# design.net
KiCad netlist of a schematic drawn in Altium Designer
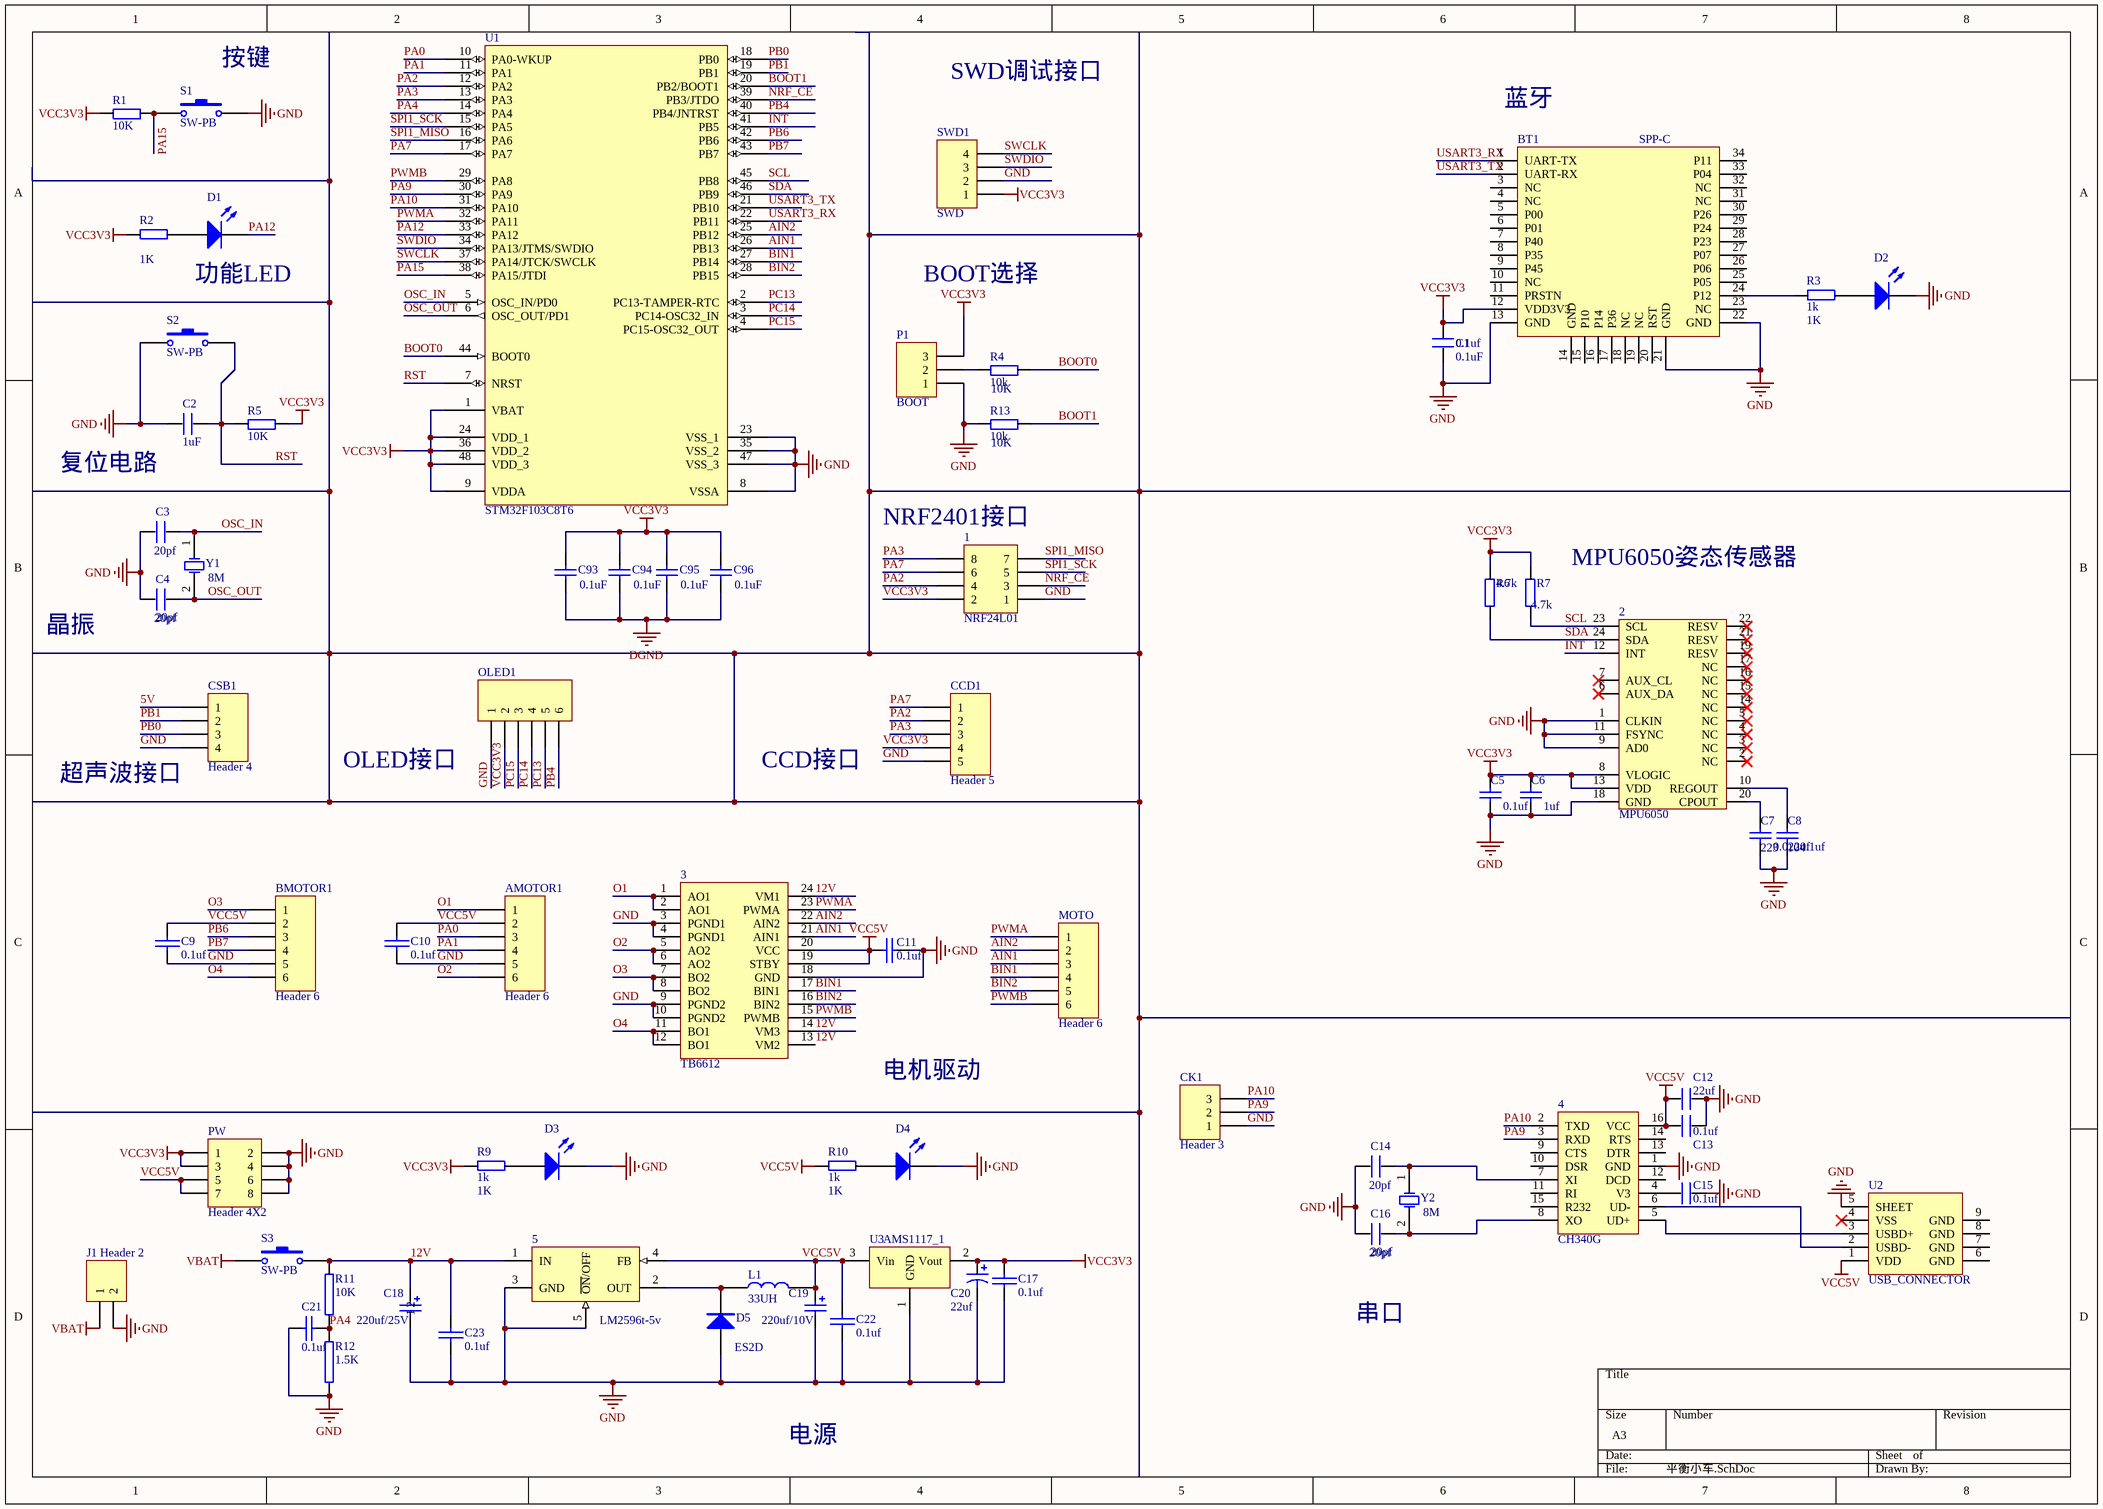
[diagram p0: 平衡小车.SchDoc]

(export (version "E")
  (design (tool "Eeschema 10.0.6"))
  (components
    (comp (ref "1")
      (value "NRF24L01")
      (footprint "LC-HDR2X4H")
      (description "Header, 4-Pin, Dual row, Right Angle")
      (fields (field (name "PUBLISHER") "Altium Limited"))
      (libsource (lib "Miscellaneous Connectors") (part "Header 4X2H"))
    )
    (comp (ref "2")
      (value "MPU6050")
      (footprint "LC-QFN-24_4x4x05P")
      (description "9轴运动处理传感器")
      (libsource (lib "Explorer STM32F407封装库") (part "MPU6050"))
    )
    (comp (ref "3") (value "TB6612") (footprint "TB6612") (libsource (lib "mzwlib") (part "TB6612")))
    (comp (ref "4") (value "CH340G") (footprint "SO-16") (libsource (lib "mzwlib") (part "CH340G")))
    (comp (ref "5")
      (value "LM2596t-5v")
      (footprint "LC-TO-263-5")
      (description "Simple Switcher 3A Step Down Voltage Regulator")
      (fields (field (name "PUBLISHER") "Altium Limited"))
      (libsource (lib "自创") (part "LM2576"))
    )
    (comp (ref "AMOTOR1")
      (value "Header 6")
      (footprint "HDR1X6")
      (description "Header, 6-Pin")
      (fields (field (name "PUBLISHER") "Altium Limited"))
      (libsource (lib "Miscellaneous Connectors") (part "Header 6"))
    )
    (comp (ref "BMOTOR1")
      (value "Header 6")
      (footprint "HDR1X6")
      (description "Header, 6-Pin")
      (fields (field (name "PUBLISHER") "Altium Limited"))
      (libsource (lib "Miscellaneous Connectors") (part "Header 6"))
    )
    (comp (ref "BT1")
      (value "SPP-C")
      (footprint "SPP-C")
      (description "sppc")
      (libsource (lib "mzwlib") (part "SPP-C"))
    )
    (comp (ref "C1")
      (value "0.1uf")
      (footprint "LC-0603_C")
      (fields (field (name "ALTIUM_VALUE") "0.1uF"))
      (libsource (lib "Explorer STM32F407封装库") (part "C"))
    )
    (comp (ref "C2")
      (value "1uF")
      (footprint "LC-0603_C")
      (libsource (lib "Explorer STM32F407封装库") (part "C_1"))
    )
    (comp (ref "C3")
      (value "20pf")
      (footprint "LC-0603_C")
      (libsource (lib "Explorer STM32F407封装库") (part "C"))
    )
    (comp (ref "C4")
      (value "20pf")
      (footprint "LC-0603_C")
      (fields (field (name "ALTIUM_VALUE") "20pf"))
      (libsource (lib "Explorer STM32F407封装库") (part "C"))
    )
    (comp (ref "C5")
      (value "0.1uf")
      (footprint "LC-0603_C")
      (description "Capacitor")
      (fields (field (name "PUBLISHER") "Altium Limited"))
      (libsource (lib "Miscellaneous Devices") (part "Cap"))
    )
    (comp (ref "C6")
      (value "1uf")
      (footprint "LC-0603_C")
      (description "Capacitor")
      (fields (field (name "PUBLISHER") "Altium Limited"))
      (libsource (lib "Miscellaneous Devices") (part "Cap"))
    )
    (comp (ref "C7")
      (value "0.022uf")
      (footprint "LC-0603_C")
      (description "Capacitor")
      (fields (field (name "ALTIUM_VALUE") "223") (field (name "PUBLISHER") "Altium Limited"))
      (libsource (lib "Miscellaneous Devices") (part "Cap"))
    )
    (comp (ref "C8")
      (value "0.1uf")
      (footprint "LC-0603_C")
      (description "Capacitor")
      (fields (field (name "ALTIUM_VALUE") "104") (field (name "PUBLISHER") "Altium Limited"))
      (libsource (lib "Miscellaneous Devices") (part "Cap"))
    )
    (comp (ref "C9") (value "0.1uf") (footprint "LC-0603_C") (libsource (lib "自创") (part "CAP")))
    (comp (ref "C10") (value "0.1uf") (footprint "LC-0603_C") (libsource (lib "自创") (part "CAP")))
    (comp (ref "C11") (value "0.1uf") (footprint "LC-0603_C") (libsource (lib "自创") (part "CAP")))
    (comp (ref "C12")
      (value "22uf")
      (footprint "LC-0805_C")
      (libsource (lib "Explorer STM32F407封装库") (part "C"))
    )
    (comp (ref "C13")
      (value "0.1uf")
      (footprint "LC-0603_C")
      (libsource (lib "Explorer STM32F407封装库") (part "C"))
    )
    (comp (ref "C14")
      (value "20pf")
      (footprint "LC-0603_C")
      (libsource (lib "Explorer STM32F407封装库") (part "C"))
    )
    (comp (ref "C15")
      (value "0.1uf")
      (footprint "LC-0603_C")
      (libsource (lib "Explorer STM32F407封装库") (part "C"))
    )
    (comp (ref "C16")
      (value "20pf")
      (footprint "LC-0603_C")
      (fields (field (name "ALTIUM_VALUE") "20pf"))
      (libsource (lib "Explorer STM32F407封装库") (part "C"))
    )
    (comp (ref "C17") (value "0.1uf") (footprint "LC-0603_C") (libsource (lib "自创") (part "CAP")))
    (comp (ref "C18")
      (value "220uf/25V")
      (footprint "100UF钽电容")
      (description "Polarized Capacitor (Radial)")
      (fields (field (name "Comment") "100Uf") (field (name "PUBLISHER") "Altium Limited"))
      (libsource (lib "") (part "Cap Pol1_1"))
    )
    (comp (ref "C19")
      (value "220uf/10V")
      (footprint "LC-1206_C")
      (description "Polarized Capacitor (Radial)")
      (fields (field (name "Comment") "100uf") (field (name "PUBLISHER") "Altium Limited"))
      (libsource (lib "自创") (part "Cap Pol1"))
    )
    (comp (ref "C20")
      (value "22uf")
      (footprint "LC-0805_R")
      (description "Polarized Capacitor (Axial)")
      (fields (field (name "PUBLISHER") "Altium Limited"))
      (libsource (lib "自创") (part "Cap Pol2"))
    )
    (comp (ref "C21") (value "0.1uf") (footprint "LC-0603_C") (libsource (lib "自创") (part "CAP")))
    (comp (ref "C22") (value "0.1uf") (footprint "LC-0603_C") (libsource (lib "自创") (part "CAP")))
    (comp (ref "C23") (value "0.1uf") (footprint "LC-0603_C") (libsource (lib "自创") (part "CAP")))
    (comp (ref "C93")
      (value "0.1uF")
      (footprint "LC-0603_C")
      (description "Capacitor")
      (fields (field (name "Comment") "0.1uf") (field (name "PUBLISHER") "Altium Limited"))
      (libsource (lib "Miscellaneous Devices") (part "Cap"))
    )
    (comp (ref "C94")
      (value "0.1uF")
      (footprint "LC-0603_C")
      (description "Capacitor")
      (fields (field (name "Comment") "0.1uf") (field (name "PUBLISHER") "Altium Limited"))
      (libsource (lib "Miscellaneous Devices") (part "Cap"))
    )
    (comp (ref "C95")
      (value "0.1uF")
      (footprint "LC-0603_C")
      (description "Capacitor")
      (fields (field (name "Comment") "0.1uf") (field (name "PUBLISHER") "Altium Limited"))
      (libsource (lib "Miscellaneous Devices") (part "Cap"))
    )
    (comp (ref "C96")
      (value "0.1uF")
      (footprint "LC-0603_C")
      (description "Capacitor")
      (fields (field (name "Comment") "0.1uf") (field (name "PUBLISHER") "Altium Limited"))
      (libsource (lib "Miscellaneous Devices") (part "Cap"))
    )
    (comp (ref "CCD1")
      (value "Header 5")
      (footprint "HDR1X5")
      (description "Header, 5-Pin")
      (fields (field (name "PUBLISHER") "Altium Limited"))
      (libsource (lib "Miscellaneous Connectors") (part "Header 5"))
    )
    (comp (ref "CK1")
      (value "Header 3")
      (footprint "HDR1X3")
      (description "Header, 3-Pin")
      (fields (field (name "PUBLISHER") "Altium Limited"))
      (libsource (lib "Miscellaneous Connectors") (part "Header 3"))
    )
    (comp (ref "CSB1")
      (value "Header 4")
      (footprint "HDR1X4")
      (description "Header, 4-Pin")
      (fields (field (name "PUBLISHER") "Altium Limited"))
      (libsource (lib "Miscellaneous Connectors") (part "Header 4"))
    )
    (comp (ref "D1")
      (value "LED0")
      (footprint "LC-0805_LED_S1")
      (description "Typical INFRARED GaAs LED")
      (fields (field (name "PUBLISHER") "Altium Limited"))
      (libsource (lib "Miscellaneous Devices") (part "LED0"))
    )
    (comp (ref "D2")
      (value "LED0")
      (footprint "LC-0805_LED_S1")
      (description "Typical INFRARED GaAs LED")
      (fields (field (name "PUBLISHER") "Altium Limited"))
      (libsource (lib "Miscellaneous Devices") (part "LED0"))
    )
    (comp (ref "D3")
      (value "LED0")
      (footprint "LC-0805_LED_S1")
      (description "Typical INFRARED GaAs LED")
      (fields (field (name "PUBLISHER") "Altium Limited"))
      (libsource (lib "Miscellaneous Devices") (part "LED0"))
    )
    (comp (ref "D4")
      (value "LED0")
      (footprint "LC-0805_LED_S1")
      (description "Typical INFRARED GaAs LED")
      (fields (field (name "PUBLISHER") "Altium Limited"))
      (libsource (lib "Miscellaneous Devices") (part "LED0"))
    )
    (comp (ref "D5") (value "ES2D") (footprint "LC-DO-213AB") (libsource (lib "自创") (part "DIODE")))
    (comp (ref "J1")
      (value "Header 2")
      (footprint "VBAT")
      (description "Header, 2-Pin")
      (fields (field (name "PUBLISHER") "Altium Limited"))
      (libsource (lib "Miscellaneous Connectors") (part "Header 2"))
    )
    (comp (ref "L1") (value "33UH") (footprint "330电感") (libsource (lib "自创") (part "Inductor")))
    (comp (ref "MOTO")
      (value "Header 6")
      (footprint "HDR1X6")
      (description "Header, 6-Pin")
      (fields (field (name "PUBLISHER") "Altium Limited"))
      (libsource (lib "Miscellaneous Connectors") (part "Header 6"))
    )
    (comp (ref "OLED1")
      (value "Header 6")
      (footprint "HDR1X6")
      (description "Header, 6-Pin")
      (fields (field (name "PUBLISHER") "Altium Limited"))
      (libsource (lib "") (part "Header 6_1"))
    )
    (comp (ref "P1")
      (value "BOOT")
      (footprint "HDR1X3")
      (description "Header, 3-Pin")
      (fields (field (name "PUBLISHER") "Altium Limited"))
      (libsource (lib "Miscellaneous Connectors") (part "Header 3"))
    )
    (comp (ref "PW")
      (value "Header 4X2")
      (footprint "HDR2X4")
      (description "Header, 4-Pin, Dual row")
      (fields (field (name "PUBLISHER") "Altium Limited"))
      (libsource (lib "Miscellaneous Connectors") (part "Header 4X2"))
    )
    (comp (ref "R1")
      (value "10K")
      (footprint "LC-0603_R")
      (libsource (lib "Explorer STM32F407封装库") (part "R_1"))
    )
    (comp (ref "R2")
      (value "1K")
      (footprint "LC-0603_R")
      (libsource (lib "Explorer STM32F407封装库") (part "R_1"))
    )
    (comp (ref "R3")
      (value "1k")
      (footprint "LC-0603_R")
      (fields (field (name "ALTIUM_VALUE") "1K"))
      (libsource (lib "Explorer STM32F407封装库") (part "R_1"))
    )
    (comp (ref "R4")
      (value "10k")
      (footprint "LC-0603_R")
      (fields (field (name "ALTIUM_VALUE") "10K"))
      (libsource (lib "Explorer STM32F407封装库") (part "R"))
    )
    (comp (ref "R5")
      (value "10K")
      (footprint "LC-0603_R")
      (libsource (lib "Explorer STM32F407封装库") (part "R_1"))
    )
    (comp (ref "R6")
      (value "4.7k")
      (footprint "LC-0603_R")
      (libsource (lib "Explorer STM32F407封装库") (part "R_1"))
    )
    (comp (ref "R7")
      (value "4.7k")
      (footprint "LC-0603_R")
      (libsource (lib "Explorer STM32F407封装库") (part "R_1"))
    )
    (comp (ref "R9")
      (value "1k")
      (footprint "LC-0603_R")
      (fields (field (name "ALTIUM_VALUE") "1K"))
      (libsource (lib "Explorer STM32F407封装库") (part "R_1"))
    )
    (comp (ref "R10")
      (value "1k")
      (footprint "LC-0603_R")
      (fields (field (name "ALTIUM_VALUE") "1K"))
      (libsource (lib "Explorer STM32F407封装库") (part "R_1"))
    )
    (comp (ref "R11") (value "10K") (footprint "LC-0603_R") (libsource (lib "自创") (part "RES")))
    (comp (ref "R12") (value "1.5K") (footprint "LC-0603_R") (libsource (lib "自创") (part "RES")))
    (comp (ref "R13")
      (value "10k")
      (footprint "LC-0603_R")
      (fields (field (name "ALTIUM_VALUE") "10K"))
      (libsource (lib "Explorer STM32F407封装库") (part "R"))
    )
    (comp (ref "S1")
      (value "SW-PB")
      (footprint "KEY")
      (description "Switch")
      (fields (field (name "PUBLISHER") "Altium Limited"))
      (libsource (lib "自创") (part "SW-PB"))
    )
    (comp (ref "S2")
      (value "SW-PB")
      (footprint "KEY")
      (description "Switch")
      (fields (field (name "PUBLISHER") "Altium Limited"))
      (libsource (lib "自创") (part "SW-PB"))
    )
    (comp (ref "S3")
      (value "SW-PB")
      (footprint "钮子开关")
      (description "Switch")
      (fields (field (name "PUBLISHER") "Altium Limited"))
      (libsource (lib "自创") (part "SW-PB"))
    )
    (comp (ref "SWD1")
      (value "SWD")
      (footprint "HDR1X4")
      (description "Header, 4-Pin")
      (fields (field (name "PUBLISHER") "Altium Limited"))
      (libsource (lib "") (part "Header 4_1"))
    )
    (comp (ref "U1")
      (value "STM32F103C8T6")
      (footprint "LC-LQFP-48_7x7x05P")
      (description "STM32 ARM-based 32-bit MCU with 64 Kbytes Flash, 48-pin LQFP, Industrial Temperature")
      (fields (field (name "PUBLISHER") "Altium Limited"))
      (libsource (lib "ST Microcontroller 32-Bit STM32") (part "STM32F103C8T6"))
    )
    (comp (ref "U2")
      (value "USB_CONNECTOR")
      (footprint "MINI_USB_FEMALE")
      (libsource (lib "mzwlib") (part "USB_CONNECTOR"))
    )
    (comp (ref "U3")
      (value "AMS1117_1")
      (footprint "LC-SOT-223")
      (description "3.3V电压转换器AMS1117")
      (libsource (lib "自创") (part "AMS1117_1"))
    )
    (comp (ref "Y1")
      (value "~")
      (footprint "LC-HC-49S")
      (description "Crystal Oscillator")
      (fields (field (name "ALTIUM_UNNAMED_1") "8M") (field (name "PUBLISHER") "Altium Limited"))
      (libsource (lib "Explorer STM32F407封装库") (part "XTAL"))
    )
    (comp (ref "Y2")
      (value "~")
      (footprint "LC-HC-49S")
      (description "Crystal Oscillator")
      (fields (field (name "ALTIUM_UNNAMED_1") "8M") (field (name "PUBLISHER") "Altium Limited"))
      (libsource (lib "Explorer STM32F407封装库") (part "XTAL"))
    )
  )
  (nets
    (net (code "1") (name "/5V") (class "Default")
      (node (ref "CSB1") (pin "1") (pinfunction "1_1") (pintype "passive"))
    )
    (net (code "2") (name "/12V") (class "Default")
      (node (ref "3") (pin "13") (pinfunction "VM2_13") (pintype "passive"))
      (node (ref "3") (pin "14") (pinfunction "VM3_14") (pintype "passive"))
      (node (ref "3") (pin "24") (pinfunction "VM1_24") (pintype "passive"))
      (node (ref "5") (pin "1") (pinfunction "IN_1") (pintype "power_in"))
      (node (ref "C18") (pin "1") (pinfunction "1_1") (pintype "passive"))
      (node (ref "C23") (pin "2") (pinfunction "2_2") (pintype "passive"))
      (node (ref "R11") (pin "2") (pinfunction "2_2") (pintype "passive"))
      (node (ref "S3") (pin "2") (pinfunction "2_2") (pintype "passive"))
    )
    (net (code "3") (name "/AIN1") (class "Default")
      (node (ref "3") (pin "21") (pinfunction "AIN1_21") (pintype "passive"))
      (node (ref "MOTO") (pin "3") (pinfunction "3_3") (pintype "passive"))
      (node (ref "U1") (pin "26") (pinfunction "PB13_26") (pintype "bidirectional"))
    )
    (net (code "4") (name "/AIN2") (class "Default")
      (node (ref "3") (pin "22") (pinfunction "AIN2_22") (pintype "passive"))
      (node (ref "MOTO") (pin "2") (pinfunction "2_2") (pintype "passive"))
      (node (ref "U1") (pin "25") (pinfunction "PB12_25") (pintype "bidirectional"))
    )
    (net (code "5") (name "/BIN1") (class "Default")
      (node (ref "3") (pin "17") (pinfunction "BIN1_17") (pintype "passive"))
      (node (ref "MOTO") (pin "4") (pinfunction "4_4") (pintype "passive"))
      (node (ref "U1") (pin "27") (pinfunction "PB14_27") (pintype "bidirectional"))
    )
    (net (code "6") (name "/BIN2") (class "Default")
      (node (ref "3") (pin "16") (pinfunction "BIN2_16") (pintype "passive"))
      (node (ref "MOTO") (pin "5") (pinfunction "5_5") (pintype "passive"))
      (node (ref "U1") (pin "28") (pinfunction "PB15_28") (pintype "bidirectional"))
    )
    (net (code "7") (name "/BOOT0") (class "Default")
      (node (ref "R4") (pin "2") (pintype "passive"))
      (node (ref "U1") (pin "44") (pinfunction "BOOT0_44") (pintype "input"))
    )
    (net (code "8") (name "/BOOT1") (class "Default")
      (node (ref "R13") (pin "2") (pintype "passive"))
      (node (ref "U1") (pin "20") (pinfunction "PB2/BOOT1_20") (pintype "bidirectional"))
    )
    (net (code "9") (name "/INT") (class "Default")
      (node (ref "2") (pin "12") (pinfunction "INT_12") (pintype "passive"))
      (node (ref "U1") (pin "41") (pinfunction "PB5_41") (pintype "bidirectional"))
    )
    (net (code "10") (name "/NRF_CE") (class "Default")
      (node (ref "1") (pin "3") (pinfunction "3_3") (pintype "passive"))
      (node (ref "U1") (pin "39") (pinfunction "PB3/JTDO_39") (pintype "bidirectional"))
    )
    (net (code "11") (name "/O1") (class "Default")
      (node (ref "3") (pin "1") (pinfunction "AO1_1") (pintype "passive"))
      (node (ref "3") (pin "2") (pinfunction "AO1_2") (pintype "passive"))
      (node (ref "AMOTOR1") (pin "1") (pinfunction "1_1") (pintype "passive"))
    )
    (net (code "12") (name "/O2") (class "Default")
      (node (ref "3") (pin "5") (pinfunction "AO2_5") (pintype "passive"))
      (node (ref "3") (pin "6") (pinfunction "AO2_6") (pintype "passive"))
      (node (ref "AMOTOR1") (pin "6") (pinfunction "6_6") (pintype "passive"))
    )
    (net (code "13") (name "/O3") (class "Default")
      (node (ref "3") (pin "7") (pinfunction "BO2_7") (pintype "passive"))
      (node (ref "3") (pin "8") (pinfunction "BO2_8") (pintype "passive"))
      (node (ref "BMOTOR1") (pin "1") (pinfunction "1_1") (pintype "passive"))
    )
    (net (code "14") (name "/O4") (class "Default")
      (node (ref "3") (pin "11") (pinfunction "BO1_11") (pintype "passive"))
      (node (ref "3") (pin "12") (pinfunction "BO1_12") (pintype "passive"))
      (node (ref "BMOTOR1") (pin "6") (pinfunction "6_6") (pintype "passive"))
    )
    (net (code "15") (name "/OSC_IN") (class "Default")
      (node (ref "C3") (pin "2") (pintype "passive"))
      (node (ref "U1") (pin "5") (pinfunction "OSC_IN/PD0_5") (pintype "input"))
      (node (ref "Y1") (pin "1") (pinfunction "OSC1_1") (pintype "passive"))
    )
    (net (code "16") (name "/OSC_OUT") (class "Default")
      (node (ref "C4") (pin "2") (pintype "passive"))
      (node (ref "U1") (pin "6") (pinfunction "OSC_OUT/PD1_6") (pintype "output"))
      (node (ref "Y1") (pin "2") (pinfunction "OSC2_2") (pintype "passive"))
    )
    (net (code "17") (name "/PA0") (class "Default")
      (node (ref "AMOTOR1") (pin "3") (pinfunction "3_3") (pintype "passive"))
      (node (ref "U1") (pin "10") (pinfunction "PA0-WKUP_10") (pintype "bidirectional"))
    )
    (net (code "18") (name "/PA1") (class "Default")
      (node (ref "AMOTOR1") (pin "4") (pinfunction "4_4") (pintype "passive"))
      (node (ref "U1") (pin "11") (pinfunction "PA1_11") (pintype "bidirectional"))
    )
    (net (code "19") (name "/PA2") (class "Default")
      (node (ref "1") (pin "4") (pinfunction "4_4") (pintype "passive"))
      (node (ref "CCD1") (pin "2") (pinfunction "2_2") (pintype "passive"))
      (node (ref "U1") (pin "12") (pinfunction "PA2_12") (pintype "bidirectional"))
    )
    (net (code "20") (name "/PA3") (class "Default")
      (node (ref "1") (pin "8") (pinfunction "8_8") (pintype "passive"))
      (node (ref "CCD1") (pin "3") (pinfunction "3_3") (pintype "passive"))
      (node (ref "U1") (pin "13") (pinfunction "PA3_13") (pintype "bidirectional"))
    )
    (net (code "21") (name "/PA4") (class "Default")
      (node (ref "C21") (pin "2") (pinfunction "2_2") (pintype "passive"))
      (node (ref "R11") (pin "1") (pinfunction "1_1") (pintype "passive"))
      (node (ref "R12") (pin "2") (pinfunction "2_2") (pintype "passive"))
      (node (ref "U1") (pin "14") (pinfunction "PA4_14") (pintype "bidirectional"))
    )
    (net (code "22") (name "/PA7") (class "Default")
      (node (ref "1") (pin "6") (pinfunction "6_6") (pintype "passive"))
      (node (ref "CCD1") (pin "1") (pinfunction "1_1") (pintype "passive"))
      (node (ref "U1") (pin "17") (pinfunction "PA7_17") (pintype "bidirectional"))
    )
    (net (code "23") (name "/PA9") (class "Default")
      (node (ref "4") (pin "3") (pinfunction "RXD_3") (pintype "passive"))
      (node (ref "CK1") (pin "2") (pinfunction "2_2") (pintype "passive"))
      (node (ref "U1") (pin "30") (pinfunction "PA9_30") (pintype "bidirectional"))
    )
    (net (code "24") (name "/PA10") (class "Default")
      (node (ref "4") (pin "2") (pinfunction "TXD_2") (pintype "passive"))
      (node (ref "CK1") (pin "3") (pinfunction "3_3") (pintype "passive"))
      (node (ref "U1") (pin "31") (pinfunction "PA10_31") (pintype "bidirectional"))
    )
    (net (code "25") (name "/PA12") (class "Default")
      (node (ref "D1") (pin "2") (pinfunction "K_2") (pintype "passive"))
      (node (ref "U1") (pin "33") (pinfunction "PA12_33") (pintype "bidirectional"))
    )
    (net (code "26") (name "/PA15") (class "Default")
      (node (ref "R1") (pin "2") (pintype "passive"))
      (node (ref "S1") (pin "1") (pinfunction "1_1") (pintype "passive"))
      (node (ref "U1") (pin "38") (pinfunction "PA15/JTDI_38") (pintype "bidirectional"))
    )
    (net (code "27") (name "/PB0") (class "Default")
      (node (ref "CSB1") (pin "3") (pinfunction "3_3") (pintype "passive"))
      (node (ref "U1") (pin "18") (pinfunction "PB0_18") (pintype "bidirectional"))
    )
    (net (code "28") (name "/PB1") (class "Default")
      (node (ref "CSB1") (pin "2") (pinfunction "2_2") (pintype "passive"))
      (node (ref "U1") (pin "19") (pinfunction "PB1_19") (pintype "bidirectional"))
    )
    (net (code "29") (name "/PB4") (class "Default")
      (node (ref "OLED1") (pin "6") (pinfunction "6_6") (pintype "passive"))
      (node (ref "U1") (pin "40") (pinfunction "PB4/JNTRST_40") (pintype "bidirectional"))
    )
    (net (code "30") (name "/PB6") (class "Default")
      (node (ref "BMOTOR1") (pin "3") (pinfunction "3_3") (pintype "passive"))
      (node (ref "U1") (pin "42") (pinfunction "PB6_42") (pintype "bidirectional"))
    )
    (net (code "31") (name "/PB7") (class "Default")
      (node (ref "BMOTOR1") (pin "4") (pinfunction "4_4") (pintype "passive"))
      (node (ref "U1") (pin "43") (pinfunction "PB7_43") (pintype "bidirectional"))
    )
    (net (code "32") (name "/PC13") (class "Default")
      (node (ref "OLED1") (pin "5") (pinfunction "5_5") (pintype "passive"))
      (node (ref "U1") (pin "2") (pinfunction "PC13-TAMPER-RTC_2") (pintype "bidirectional"))
    )
    (net (code "33") (name "/PC14") (class "Default")
      (node (ref "OLED1") (pin "4") (pinfunction "4_4") (pintype "passive"))
      (node (ref "U1") (pin "3") (pinfunction "PC14-OSC32_IN_3") (pintype "bidirectional"))
    )
    (net (code "34") (name "/PC15") (class "Default")
      (node (ref "OLED1") (pin "3") (pinfunction "3_3") (pintype "passive"))
      (node (ref "U1") (pin "4") (pinfunction "PC15-OSC32_OUT_4") (pintype "bidirectional"))
    )
    (net (code "35") (name "/PWMA") (class "Default")
      (node (ref "3") (pin "23") (pinfunction "PWMA_23") (pintype "passive"))
      (node (ref "MOTO") (pin "1") (pinfunction "1_1") (pintype "passive"))
      (node (ref "U1") (pin "32") (pinfunction "PA11_32") (pintype "bidirectional"))
    )
    (net (code "36") (name "/PWMB") (class "Default")
      (node (ref "3") (pin "15") (pinfunction "PWMB_15") (pintype "passive"))
      (node (ref "MOTO") (pin "6") (pinfunction "6_6") (pintype "passive"))
      (node (ref "U1") (pin "29") (pinfunction "PA8_29") (pintype "bidirectional"))
    )
    (net (code "37") (name "/RST") (class "Default")
      (node (ref "C2") (pin "2") (pintype "passive"))
      (node (ref "R5") (pin "1") (pintype "passive"))
      (node (ref "S2") (pin "2") (pinfunction "2_2") (pintype "passive"))
      (node (ref "U1") (pin "7") (pinfunction "NRST_7") (pintype "bidirectional"))
    )
    (net (code "38") (name "/SCL") (class "Default")
      (node (ref "2") (pin "23") (pinfunction "SCL_23") (pintype "passive"))
      (node (ref "R7") (pin "2") (pintype "passive"))
      (node (ref "U1") (pin "45") (pinfunction "PB8_45") (pintype "bidirectional"))
    )
    (net (code "39") (name "/SDA") (class "Default")
      (node (ref "2") (pin "24") (pinfunction "SDA_24") (pintype "passive"))
      (node (ref "R6") (pin "2") (pintype "passive"))
      (node (ref "U1") (pin "46") (pinfunction "PB9_46") (pintype "bidirectional"))
    )
    (net (code "40") (name "/SPI1_MISO") (class "Default")
      (node (ref "1") (pin "7") (pinfunction "7_7") (pintype "passive"))
      (node (ref "U1") (pin "16") (pinfunction "PA6_16") (pintype "bidirectional"))
    )
    (net (code "41") (name "/SPI1_SCK") (class "Default")
      (node (ref "1") (pin "5") (pinfunction "5_5") (pintype "passive"))
      (node (ref "U1") (pin "15") (pinfunction "PA5_15") (pintype "bidirectional"))
    )
    (net (code "42") (name "/SWCLK") (class "Default")
      (node (ref "SWD1") (pin "4") (pinfunction "4_4") (pintype "passive"))
      (node (ref "U1") (pin "37") (pinfunction "PA14/JTCK/SWCLK_37") (pintype "bidirectional"))
    )
    (net (code "43") (name "/SWDIO") (class "Default")
      (node (ref "SWD1") (pin "3") (pinfunction "3_3") (pintype "passive"))
      (node (ref "U1") (pin "34") (pinfunction "PA13/JTMS/SWDIO_34") (pintype "bidirectional"))
    )
    (net (code "44") (name "/USART3_RX") (class "Default")
      (node (ref "BT1") (pin "1") (pinfunction "UART-TX_1") (pintype "passive"))
      (node (ref "U1") (pin "22") (pinfunction "PB11_22") (pintype "bidirectional"))
    )
    (net (code "45") (name "/USART3_TX") (class "Default")
      (node (ref "BT1") (pin "2") (pinfunction "UART-RX_2") (pintype "passive"))
      (node (ref "U1") (pin "21") (pinfunction "PB10_21") (pintype "bidirectional"))
    )
    (net (code "46") (name "DGND") (class "Default")
      (node (ref "C93") (pin "1") (pinfunction "1_1") (pintype "passive"))
      (node (ref "C94") (pin "1") (pinfunction "1_1") (pintype "passive"))
      (node (ref "C95") (pin "1") (pinfunction "1_1") (pintype "passive"))
      (node (ref "C96") (pin "1") (pinfunction "1_1") (pintype "passive"))
    )
    (net (code "47") (name "GND") (class "Default")
      (node (ref "1") (pin "1") (pinfunction "1_1") (pintype "passive"))
      (node (ref "2") (pin "1") (pinfunction "CLKIN_1") (pintype "passive"))
      (node (ref "2") (pin "11") (pinfunction "FSYNC_11") (pintype "passive"))
      (node (ref "2") (pin "18") (pinfunction "GND_18") (pintype "passive"))
      (node (ref "2") (pin "9") (pinfunction "AD0_9") (pintype "passive"))
      (node (ref "3") (pin "10") (pinfunction "PGND2_10") (pintype "passive"))
      (node (ref "3") (pin "18") (pinfunction "GND_18") (pintype "passive"))
      (node (ref "3") (pin "3") (pinfunction "PGND1_3") (pintype "passive"))
      (node (ref "3") (pin "4") (pinfunction "PGND1_4") (pintype "passive"))
      (node (ref "3") (pin "9") (pinfunction "PGND2_9") (pintype "passive"))
      (node (ref "4") (pin "1") (pinfunction "GND_1") (pintype "passive"))
      (node (ref "5") (pin "3") (pinfunction "GND_3") (pintype "power_in"))
      (node (ref "5") (pin "5") (pinfunction "~{ON}/OFF_5") (pintype "input"))
      (node (ref "AMOTOR1") (pin "5") (pinfunction "5_5") (pintype "passive"))
      (node (ref "BMOTOR1") (pin "5") (pinfunction "5_5") (pintype "passive"))
      (node (ref "BT1") (pin "13") (pinfunction "GND_13") (pintype "passive"))
      (node (ref "BT1") (pin "21") (pinfunction "GND_21") (pintype "passive"))
      (node (ref "BT1") (pin "22") (pinfunction "GND_22") (pintype "passive"))
      (node (ref "C1") (pin "1") (pintype "passive"))
      (node (ref "C10") (pin "2") (pinfunction "2_2") (pintype "passive"))
      (node (ref "C11") (pin "1") (pinfunction "1_1") (pintype "passive"))
      (node (ref "C12") (pin "1") (pintype "passive"))
      (node (ref "C13") (pin "2") (pintype "passive"))
      (node (ref "C14") (pin "1") (pintype "passive"))
      (node (ref "C15") (pin "2") (pintype "passive"))
      (node (ref "C16") (pin "1") (pintype "passive"))
      (node (ref "C17") (pin "1") (pinfunction "1_1") (pintype "passive"))
      (node (ref "C18") (pin "2") (pinfunction "2_2") (pintype "passive"))
      (node (ref "C19") (pin "2") (pinfunction "2_2") (pintype "passive"))
      (node (ref "C2") (pin "1") (pintype "passive"))
      (node (ref "C20") (pin "2") (pinfunction "2_2") (pintype "passive"))
      (node (ref "C21") (pin "1") (pinfunction "1_1") (pintype "passive"))
      (node (ref "C22") (pin "1") (pinfunction "1_1") (pintype "passive"))
      (node (ref "C23") (pin "1") (pinfunction "1_1") (pintype "passive"))
      (node (ref "C3") (pin "1") (pintype "passive"))
      (node (ref "C4") (pin "1") (pintype "passive"))
      (node (ref "C5") (pin "1") (pinfunction "1_1") (pintype "passive"))
      (node (ref "C6") (pin "1") (pinfunction "1_1") (pintype "passive"))
      (node (ref "C7") (pin "1") (pinfunction "1_1") (pintype "passive"))
      (node (ref "C8") (pin "1") (pinfunction "1_1") (pintype "passive"))
      (node (ref "C9") (pin "2") (pinfunction "2_2") (pintype "passive"))
      (node (ref "CCD1") (pin "5") (pinfunction "5_5") (pintype "passive"))
      (node (ref "CK1") (pin "1") (pinfunction "1_1") (pintype "passive"))
      (node (ref "CSB1") (pin "4") (pinfunction "4_4") (pintype "passive"))
      (node (ref "D2") (pin "2") (pinfunction "K_2") (pintype "passive"))
      (node (ref "D3") (pin "2") (pinfunction "K_2") (pintype "passive"))
      (node (ref "D4") (pin "2") (pinfunction "K_2") (pintype "passive"))
      (node (ref "D5") (pin "1") (pinfunction "1_1") (pintype "passive"))
      (node (ref "J1") (pin "2") (pinfunction "2_2") (pintype "passive"))
      (node (ref "OLED1") (pin "1") (pinfunction "1_1") (pintype "passive"))
      (node (ref "P1") (pin "1") (pinfunction "1_1") (pintype "passive"))
      (node (ref "PW") (pin "2") (pinfunction "2_2") (pintype "passive"))
      (node (ref "PW") (pin "4") (pinfunction "4_4") (pintype "passive"))
      (node (ref "PW") (pin "6") (pinfunction "6_6") (pintype "passive"))
      (node (ref "PW") (pin "8") (pinfunction "8_8") (pintype "passive"))
      (node (ref "R12") (pin "1") (pinfunction "1_1") (pintype "passive"))
      (node (ref "R13") (pin "1") (pintype "passive"))
      (node (ref "S1") (pin "2") (pinfunction "2_2") (pintype "passive"))
      (node (ref "S2") (pin "1") (pinfunction "1_1") (pintype "passive"))
      (node (ref "SWD1") (pin "2") (pinfunction "2_2") (pintype "passive"))
      (node (ref "U1") (pin "23") (pinfunction "VSS_1_23") (pintype "power_in"))
      (node (ref "U1") (pin "35") (pinfunction "VSS_2_35") (pintype "power_in"))
      (node (ref "U1") (pin "47") (pinfunction "VSS_3_47") (pintype "power_in"))
      (node (ref "U1") (pin "8") (pinfunction "VSSA_8") (pintype "power_in"))
      (node (ref "U2") (pin "5") (pinfunction "SHEET_5") (pintype "passive"))
      (node (ref "U3") (pin "1") (pinfunction "GND_1") (pintype "passive"))
    )
    (net (code "48") (name "Net-(2-CPOUT)") (class "Default")
      (node (ref "2") (pin "20") (pinfunction "CPOUT_20") (pintype "passive"))
      (node (ref "C7") (pin "2") (pinfunction "2_2") (pintype "passive"))
    )
    (net (code "49") (name "Net-(2-REGOUT)") (class "Default")
      (node (ref "2") (pin "10") (pinfunction "REGOUT_10") (pintype "passive"))
      (node (ref "C8") (pin "2") (pinfunction "2_2") (pintype "passive"))
    )
    (net (code "50") (name "Net-(4-UD+)") (class "Default")
      (node (ref "4") (pin "5") (pinfunction "UD+_5") (pintype "passive"))
      (node (ref "U2") (pin "3") (pinfunction "USBD+_3") (pintype "passive"))
    )
    (net (code "51") (name "Net-(4-UD-)") (class "Default")
      (node (ref "4") (pin "6") (pinfunction "UD-_6") (pintype "passive"))
      (node (ref "U2") (pin "2") (pinfunction "USBD-_2") (pintype "passive"))
    )
    (net (code "52") (name "Net-(4-V3)") (class "Default")
      (node (ref "4") (pin "4") (pinfunction "V3_4") (pintype "passive"))
      (node (ref "C15") (pin "1") (pintype "passive"))
    )
    (net (code "53") (name "Net-(4-XI)") (class "Default")
      (node (ref "4") (pin "7") (pinfunction "XI_7") (pintype "passive"))
      (node (ref "C14") (pin "2") (pintype "passive"))
      (node (ref "Y2") (pin "1") (pinfunction "OSC1_1") (pintype "passive"))
    )
    (net (code "54") (name "Net-(4-XO)") (class "Default")
      (node (ref "4") (pin "8") (pinfunction "XO_8") (pintype "passive"))
      (node (ref "C16") (pin "2") (pintype "passive"))
      (node (ref "Y2") (pin "2") (pinfunction "OSC2_2") (pintype "passive"))
    )
    (net (code "55") (name "Net-(5-OUT)") (class "Default")
      (node (ref "5") (pin "2") (pinfunction "OUT_2") (pintype "power_in"))
      (node (ref "D5") (pin "2") (pinfunction "2_2") (pintype "passive"))
      (node (ref "L1") (pin "1") (pinfunction "1_1") (pintype "passive"))
    )
    (net (code "56") (name "Net-(BT1-P12)") (class "Default")
      (node (ref "BT1") (pin "24") (pinfunction "P12_24") (pintype "passive"))
      (node (ref "R3") (pin "2") (pintype "passive"))
    )
    (net (code "57") (name "Net-(D1-A)") (class "Default")
      (node (ref "D1") (pin "1") (pinfunction "A_1") (pintype "passive"))
      (node (ref "R2") (pin "1") (pintype "passive"))
    )
    (net (code "58") (name "Net-(D2-A)") (class "Default")
      (node (ref "D2") (pin "1") (pinfunction "A_1") (pintype "passive"))
      (node (ref "R3") (pin "1") (pintype "passive"))
    )
    (net (code "59") (name "Net-(D3-A)") (class "Default")
      (node (ref "D3") (pin "1") (pinfunction "A_1") (pintype "passive"))
      (node (ref "R9") (pin "1") (pintype "passive"))
    )
    (net (code "60") (name "Net-(D4-A)") (class "Default")
      (node (ref "D4") (pin "1") (pinfunction "A_1") (pintype "passive"))
      (node (ref "R10") (pin "1") (pintype "passive"))
    )
    (net (code "61") (name "Net-(P1-Pad2)") (class "Default")
      (node (ref "P1") (pin "2") (pinfunction "2_2") (pintype "passive"))
      (node (ref "R4") (pin "1") (pintype "passive"))
    )
    (net (code "62") (name "VBAT") (class "Default")
      (node (ref "J1") (pin "1") (pinfunction "1_1") (pintype "passive"))
      (node (ref "S3") (pin "1") (pinfunction "1_1") (pintype "passive"))
    )
    (net (code "63") (name "VCC3V3") (class "Default")
      (node (ref "1") (pin "2") (pinfunction "2_2") (pintype "passive"))
      (node (ref "2") (pin "13") (pinfunction "VDD_13") (pintype "passive"))
      (node (ref "2") (pin "8") (pinfunction "VLOGIC_8") (pintype "passive"))
      (node (ref "BT1") (pin "12") (pinfunction "VDD3V3_12") (pintype "passive"))
      (node (ref "C1") (pin "2") (pintype "passive"))
      (node (ref "C17") (pin "2") (pinfunction "2_2") (pintype "passive"))
      (node (ref "C20") (pin "1") (pinfunction "1_1") (pintype "passive"))
      (node (ref "C5") (pin "2") (pinfunction "2_2") (pintype "passive"))
      (node (ref "C6") (pin "2") (pinfunction "2_2") (pintype "passive"))
      (node (ref "C93") (pin "2") (pinfunction "2_2") (pintype "passive"))
      (node (ref "C94") (pin "2") (pinfunction "2_2") (pintype "passive"))
      (node (ref "C95") (pin "2") (pinfunction "2_2") (pintype "passive"))
      (node (ref "C96") (pin "2") (pinfunction "2_2") (pintype "passive"))
      (node (ref "CCD1") (pin "4") (pinfunction "4_4") (pintype "passive"))
      (node (ref "OLED1") (pin "2") (pinfunction "2_2") (pintype "passive"))
      (node (ref "P1") (pin "3") (pinfunction "3_3") (pintype "passive"))
      (node (ref "PW") (pin "1") (pinfunction "1_1") (pintype "passive"))
      (node (ref "PW") (pin "3") (pinfunction "3_3") (pintype "passive"))
      (node (ref "R1") (pin "1") (pintype "passive"))
      (node (ref "R2") (pin "2") (pintype "passive"))
      (node (ref "R5") (pin "2") (pintype "passive"))
      (node (ref "R6") (pin "1") (pintype "passive"))
      (node (ref "R7") (pin "1") (pintype "passive"))
      (node (ref "R9") (pin "2") (pintype "passive"))
      (node (ref "SWD1") (pin "1") (pinfunction "1_1") (pintype "passive"))
      (node (ref "U1") (pin "1") (pinfunction "VBAT_1") (pintype "power_in"))
      (node (ref "U1") (pin "24") (pinfunction "VDD_1_24") (pintype "power_in"))
      (node (ref "U1") (pin "36") (pinfunction "VDD_2_36") (pintype "power_in"))
      (node (ref "U1") (pin "48") (pinfunction "VDD_3_48") (pintype "power_in"))
      (node (ref "U1") (pin "9") (pinfunction "VDDA_9") (pintype "power_in"))
      (node (ref "U3") (pin "2") (pinfunction "Vout_2") (pintype "passive"))
    )
    (net (code "64") (name "VCC5V") (class "Default")
      (node (ref "3") (pin "19") (pinfunction "STBY_19") (pintype "passive"))
      (node (ref "3") (pin "20") (pinfunction "VCC_20") (pintype "passive"))
      (node (ref "4") (pin "16") (pinfunction "VCC_16") (pintype "passive"))
      (node (ref "5") (pin "4") (pinfunction "FB_4") (pintype "input"))
      (node (ref "AMOTOR1") (pin "2") (pinfunction "2_2") (pintype "passive"))
      (node (ref "BMOTOR1") (pin "2") (pinfunction "2_2") (pintype "passive"))
      (node (ref "C10") (pin "1") (pinfunction "1_1") (pintype "passive"))
      (node (ref "C11") (pin "2") (pinfunction "2_2") (pintype "passive"))
      (node (ref "C12") (pin "2") (pintype "passive"))
      (node (ref "C13") (pin "1") (pintype "passive"))
      (node (ref "C19") (pin "1") (pinfunction "1_1") (pintype "passive"))
      (node (ref "C22") (pin "2") (pinfunction "2_2") (pintype "passive"))
      (node (ref "C9") (pin "1") (pinfunction "1_1") (pintype "passive"))
      (node (ref "L1") (pin "2") (pinfunction "2_2") (pintype "passive"))
      (node (ref "PW") (pin "5") (pinfunction "5_5") (pintype "passive"))
      (node (ref "PW") (pin "7") (pinfunction "7_7") (pintype "passive"))
      (node (ref "R10") (pin "2") (pintype "passive"))
      (node (ref "U2") (pin "1") (pinfunction "VDD_1") (pintype "passive"))
      (node (ref "U3") (pin "3") (pinfunction "Vin_3") (pintype "passive"))
    )
    (net (code "65") (name "unconnected-(2-AUX_CL-Pad7)") (class "Default")
      (node (ref "2") (pin "7") (pinfunction "AUX_CL_7") (pintype "passive+no_connect"))
    )
    (net (code "66") (name "unconnected-(2-AUX_DA-Pad6)") (class "Default")
      (node (ref "2") (pin "6") (pinfunction "AUX_DA_6") (pintype "passive+no_connect"))
    )
    (net (code "67") (name "unconnected-(2-NC-Pad2)") (class "Default")
      (node (ref "2") (pin "2") (pinfunction "NC_2") (pintype "passive+no_connect"))
    )
    (net (code "68") (name "unconnected-(2-NC-Pad3)") (class "Default")
      (node (ref "2") (pin "3") (pinfunction "NC_3") (pintype "passive+no_connect"))
    )
    (net (code "69") (name "unconnected-(2-NC-Pad4)") (class "Default")
      (node (ref "2") (pin "4") (pinfunction "NC_4") (pintype "passive+no_connect"))
    )
    (net (code "70") (name "unconnected-(2-NC-Pad5)") (class "Default")
      (node (ref "2") (pin "5") (pinfunction "NC_5") (pintype "passive+no_connect"))
    )
    (net (code "71") (name "unconnected-(2-NC-Pad14)") (class "Default")
      (node (ref "2") (pin "14") (pinfunction "NC_14") (pintype "passive+no_connect"))
    )
    (net (code "72") (name "unconnected-(2-NC-Pad15)") (class "Default")
      (node (ref "2") (pin "15") (pinfunction "NC_15") (pintype "passive+no_connect"))
    )
    (net (code "73") (name "unconnected-(2-NC-Pad16)") (class "Default")
      (node (ref "2") (pin "16") (pinfunction "NC_16") (pintype "passive+no_connect"))
    )
    (net (code "74") (name "unconnected-(2-NC-Pad17)") (class "Default")
      (node (ref "2") (pin "17") (pinfunction "NC_17") (pintype "passive+no_connect"))
    )
    (net (code "75") (name "unconnected-(2-RESV-Pad19)") (class "Default")
      (node (ref "2") (pin "19") (pinfunction "RESV_19") (pintype "passive+no_connect"))
    )
    (net (code "76") (name "unconnected-(2-RESV-Pad21)") (class "Default")
      (node (ref "2") (pin "21") (pinfunction "RESV_21") (pintype "passive+no_connect"))
    )
    (net (code "77") (name "unconnected-(2-RESV-Pad22)") (class "Default")
      (node (ref "2") (pin "22") (pinfunction "RESV_22") (pintype "passive+no_connect"))
    )
    (net (code "78") (name "unconnected-(4-CTS-Pad9)") (class "Default")
      (node (ref "4") (pin "9") (pinfunction "CTS_9") (pintype "passive"))
    )
    (net (code "79") (name "unconnected-(4-DCD-Pad12)") (class "Default")
      (node (ref "4") (pin "12") (pinfunction "DCD_12") (pintype "passive"))
    )
    (net (code "80") (name "unconnected-(4-DSR-Pad10)") (class "Default")
      (node (ref "4") (pin "10") (pinfunction "DSR_10") (pintype "passive"))
    )
    (net (code "81") (name "unconnected-(4-DTR-Pad13)") (class "Default")
      (node (ref "4") (pin "13") (pinfunction "DTR_13") (pintype "passive"))
    )
    (net (code "82") (name "unconnected-(4-R232-Pad15)") (class "Default")
      (node (ref "4") (pin "15") (pinfunction "R232_15") (pintype "passive"))
    )
    (net (code "83") (name "unconnected-(4-RI-Pad11)") (class "Default")
      (node (ref "4") (pin "11") (pinfunction "RI_11") (pintype "passive"))
    )
    (net (code "84") (name "unconnected-(4-RTS-Pad14)") (class "Default")
      (node (ref "4") (pin "14") (pinfunction "RTS_14") (pintype "passive"))
    )
    (net (code "85") (name "unconnected-(BT1-GND-Pad14)") (class "Default")
      (node (ref "BT1") (pin "14") (pinfunction "GND_14") (pintype "passive"))
    )
    (net (code "86") (name "unconnected-(BT1-NC-Pad3)") (class "Default")
      (node (ref "BT1") (pin "3") (pinfunction "NC_3") (pintype "passive"))
    )
    (net (code "87") (name "unconnected-(BT1-NC-Pad4)") (class "Default")
      (node (ref "BT1") (pin "4") (pinfunction "NC_4") (pintype "passive"))
    )
    (net (code "88") (name "unconnected-(BT1-NC-Pad10)") (class "Default")
      (node (ref "BT1") (pin "10") (pinfunction "NC_10") (pintype "passive"))
    )
    (net (code "89") (name "unconnected-(BT1-NC-Pad18)") (class "Default")
      (node (ref "BT1") (pin "18") (pinfunction "NC_18") (pintype "passive"))
    )
    (net (code "90") (name "unconnected-(BT1-NC-Pad19)") (class "Default")
      (node (ref "BT1") (pin "19") (pinfunction "NC_19") (pintype "passive"))
    )
    (net (code "91") (name "unconnected-(BT1-NC-Pad23)") (class "Default")
      (node (ref "BT1") (pin "23") (pinfunction "NC_23") (pintype "passive"))
    )
    (net (code "92") (name "unconnected-(BT1-NC-Pad31)") (class "Default")
      (node (ref "BT1") (pin "31") (pinfunction "NC_31") (pintype "passive"))
    )
    (net (code "93") (name "unconnected-(BT1-NC-Pad32)") (class "Default")
      (node (ref "BT1") (pin "32") (pinfunction "NC_32") (pintype "passive"))
    )
    (net (code "94") (name "unconnected-(BT1-P00-Pad5)") (class "Default")
      (node (ref "BT1") (pin "5") (pinfunction "P00_5") (pintype "passive"))
    )
    (net (code "95") (name "unconnected-(BT1-P01-Pad6)") (class "Default")
      (node (ref "BT1") (pin "6") (pinfunction "P01_6") (pintype "passive"))
    )
    (net (code "96") (name "unconnected-(BT1-P04-Pad33)") (class "Default")
      (node (ref "BT1") (pin "33") (pinfunction "P04_33") (pintype "passive"))
    )
    (net (code "97") (name "unconnected-(BT1-P05-Pad25)") (class "Default")
      (node (ref "BT1") (pin "25") (pinfunction "P05_25") (pintype "passive"))
    )
    (net (code "98") (name "unconnected-(BT1-P06-Pad26)") (class "Default")
      (node (ref "BT1") (pin "26") (pinfunction "P06_26") (pintype "passive"))
    )
    (net (code "99") (name "unconnected-(BT1-P07-Pad27)") (class "Default")
      (node (ref "BT1") (pin "27") (pinfunction "P07_27") (pintype "passive"))
    )
    (net (code "100") (name "unconnected-(BT1-P10-Pad15)") (class "Default")
      (node (ref "BT1") (pin "15") (pinfunction "P10_15") (pintype "passive"))
    )
    (net (code "101") (name "unconnected-(BT1-P11-Pad34)") (class "Default")
      (node (ref "BT1") (pin "34") (pinfunction "P11_34") (pintype "passive"))
    )
    (net (code "102") (name "unconnected-(BT1-P14-Pad16)") (class "Default")
      (node (ref "BT1") (pin "16") (pinfunction "P14_16") (pintype "passive"))
    )
    (net (code "103") (name "unconnected-(BT1-P23-Pad28)") (class "Default")
      (node (ref "BT1") (pin "28") (pinfunction "P23_28") (pintype "passive"))
    )
    (net (code "104") (name "unconnected-(BT1-P24-Pad29)") (class "Default")
      (node (ref "BT1") (pin "29") (pinfunction "P24_29") (pintype "passive"))
    )
    (net (code "105") (name "unconnected-(BT1-P26-Pad30)") (class "Default")
      (node (ref "BT1") (pin "30") (pinfunction "P26_30") (pintype "passive"))
    )
    (net (code "106") (name "unconnected-(BT1-P35-Pad8)") (class "Default")
      (node (ref "BT1") (pin "8") (pinfunction "P35_8") (pintype "passive"))
    )
    (net (code "107") (name "unconnected-(BT1-P36-Pad17)") (class "Default")
      (node (ref "BT1") (pin "17") (pinfunction "P36_17") (pintype "passive"))
    )
    (net (code "108") (name "unconnected-(BT1-P40-Pad7)") (class "Default")
      (node (ref "BT1") (pin "7") (pinfunction "P40_7") (pintype "passive"))
    )
    (net (code "109") (name "unconnected-(BT1-P45-Pad9)") (class "Default")
      (node (ref "BT1") (pin "9") (pinfunction "P45_9") (pintype "passive"))
    )
    (net (code "110") (name "unconnected-(BT1-PRSTN-Pad11)") (class "Default")
      (node (ref "BT1") (pin "11") (pinfunction "PRSTN_11") (pintype "passive"))
    )
    (net (code "111") (name "unconnected-(BT1-RST-Pad20)") (class "Default")
      (node (ref "BT1") (pin "20") (pinfunction "RST_20") (pintype "passive"))
    )
    (net (code "112") (name "unconnected-(U2-GND-Pad6)") (class "Default")
      (node (ref "U2") (pin "6") (pinfunction "GND_6") (pintype "passive"))
    )
    (net (code "113") (name "unconnected-(U2-GND-Pad7)") (class "Default")
      (node (ref "U2") (pin "7") (pinfunction "GND_7") (pintype "passive"))
    )
    (net (code "114") (name "unconnected-(U2-GND-Pad8)") (class "Default")
      (node (ref "U2") (pin "8") (pinfunction "GND_8") (pintype "passive"))
    )
    (net (code "115") (name "unconnected-(U2-GND-Pad9)") (class "Default")
      (node (ref "U2") (pin "9") (pinfunction "GND_9") (pintype "passive"))
    )
    (net (code "116") (name "unconnected-(U2-VSS-Pad4)") (class "Default")
      (node (ref "U2") (pin "4") (pinfunction "VSS_4") (pintype "passive+no_connect"))
    )
  )
)
